# main-board.net
KiCad netlist of a schematic drawn in EAGLE
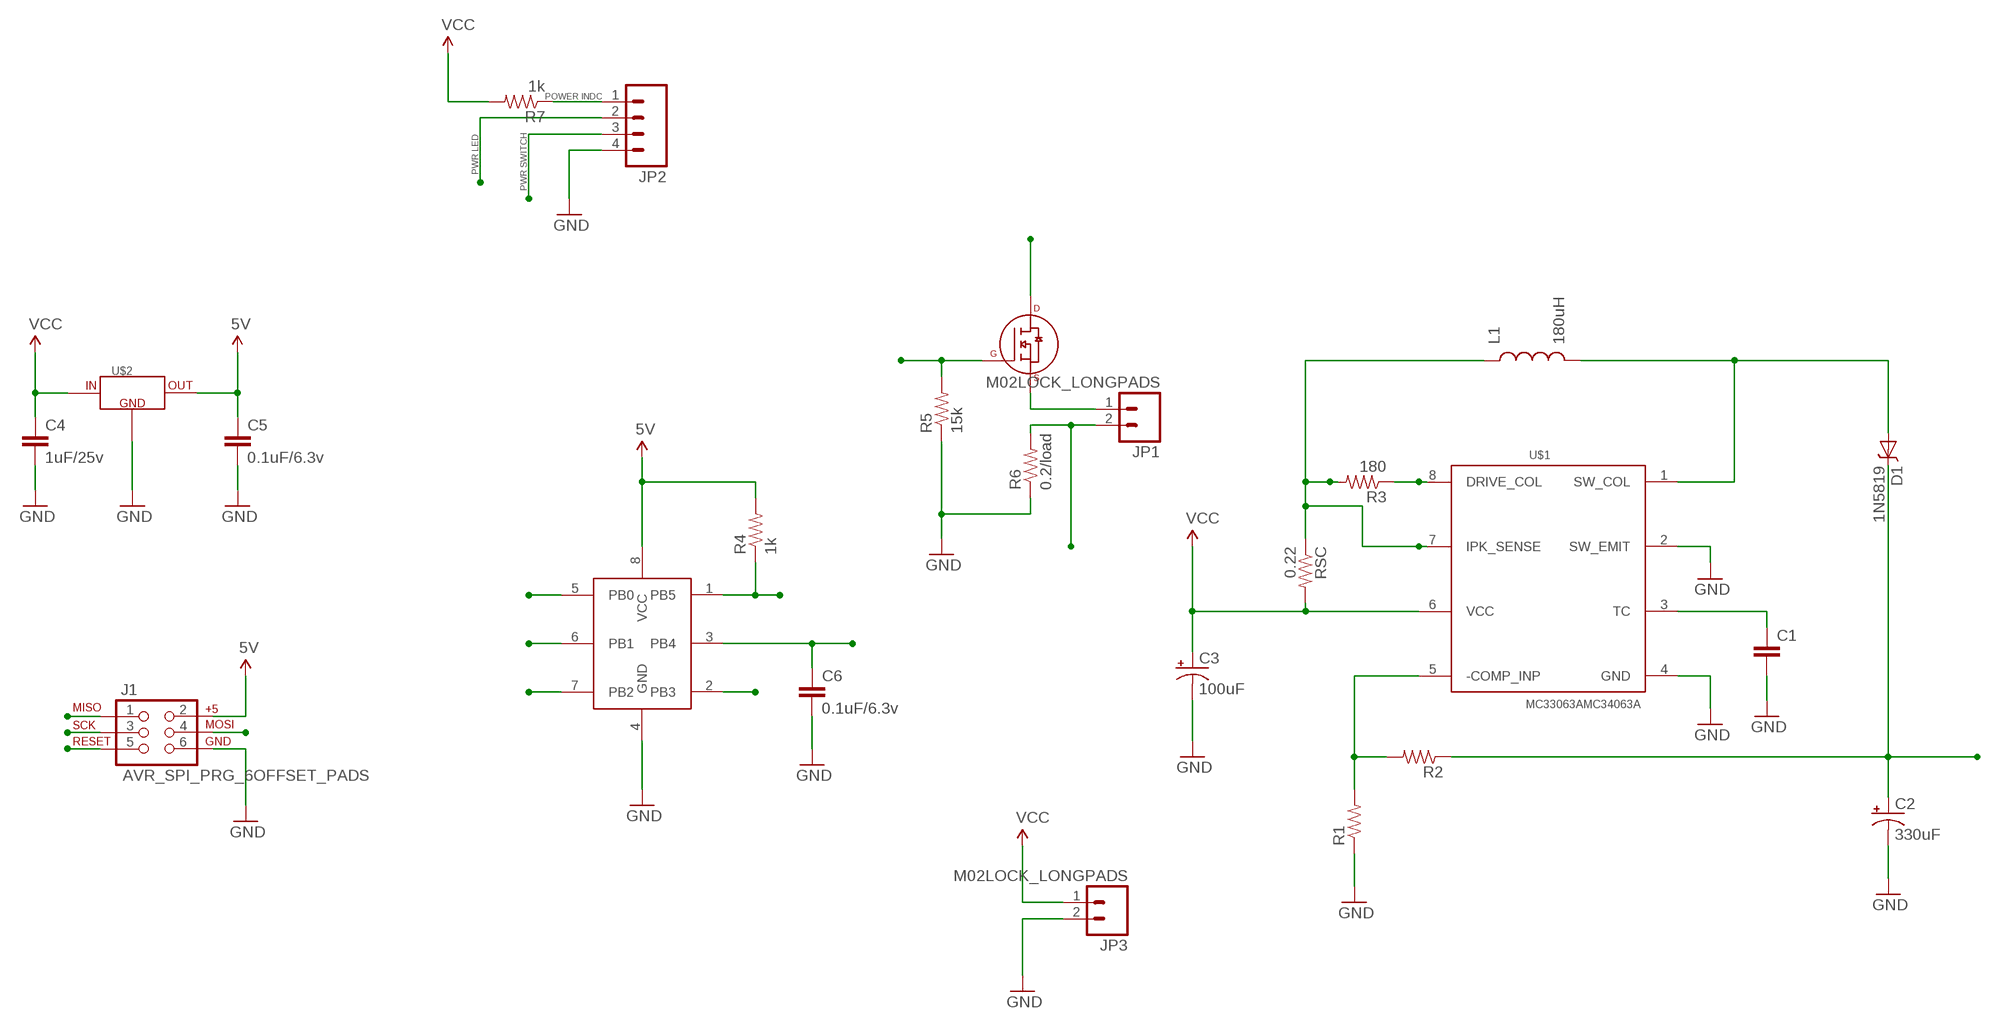
[diagram p0: schematic, sheet 1]

(export (version "E")
  (design (tool "Eeschema 10.0.6"))
  (components
    (comp (ref "C1")
      (value "CAP0603-CAP")
      (footprint "eagle-import:0603-CAP")
      (libsource (lib "eagle-import") (part "SparkFun-Passives_CAP0603-CAP"))
    )
    (comp (ref "C2")
      (value "330uF")
      (footprint "eagle-import:PANASONIC_D")
      (libsource (lib "eagle-import") (part "CPOL-USD"))
    )
    (comp (ref "C3")
      (value "100uF")
      (footprint "eagle-import:PANASONIC_D")
      (libsource (lib "eagle-import") (part "CPOL-USD"))
    )
    (comp (ref "C4")
      (value "1uF/25v")
      (footprint "eagle-import:0603-CAP")
      (libsource (lib "eagle-import") (part "CAP0603-CAP"))
    )
    (comp (ref "C5")
      (value "0.1uF/6.3v")
      (footprint "eagle-import:0603-CAP")
      (libsource (lib "eagle-import") (part "CAP0603-CAP"))
    )
    (comp (ref "C6")
      (value "0.1uF/6.3v")
      (footprint "eagle-import:0603-CAP")
      (libsource (lib "eagle-import") (part "CAP0603-CAP"))
    )
    (comp (ref "D1")
      (value "1N5819")
      (footprint "eagle-import:SMA-DIODE")
      (libsource (lib "eagle-import") (part "DIODE-SCHOTTKY_"))
    )
    (comp (ref "J1")
      (value "AVR_SPI_PRG_6OFFSET_PADS")
      (footprint "eagle-import:2X3_OFFSET")
      (libsource (lib "eagle-import") (part "AVR_SPI_PRG_6OFFSET_PADS"))
    )
    (comp (ref "JP1")
      (value "M02LOCK_LONGPADS")
      (footprint "eagle-import:1X02_LOCK_LONGPADS")
      (libsource (lib "eagle-import") (part "M02LOCK_LONGPADS"))
    )
    (comp (ref "JP2")
      (value "M04LONGPADS")
      (footprint "eagle-import:1X04_LONGPADS")
      (libsource (lib "eagle-import") (part "M04LONGPADS"))
    )
    (comp (ref "JP3")
      (value "M02LOCK_LONGPADS")
      (footprint "eagle-import:1X02_LOCK_LONGPADS")
      (libsource (lib "eagle-import") (part "M02LOCK_LONGPADS"))
    )
    (comp (ref "L1")
      (value "180uH")
      (footprint "eagle-import:CDRH125")
      (libsource (lib "eagle-import") (part "INDUCTORPWR"))
    )
    (comp (ref "R1")
      (value "RESISTOR0603")
      (footprint "eagle-import:0603-RES")
      (libsource (lib "eagle-import") (part "RESISTOR0603"))
    )
    (comp (ref "R2")
      (value "RESISTOR0603")
      (footprint "eagle-import:0603-RES")
      (libsource (lib "eagle-import") (part "RESISTOR0603"))
    )
    (comp (ref "R3")
      (value "180")
      (footprint "eagle-import:0603-RES")
      (libsource (lib "eagle-import") (part "RESISTOR0603"))
    )
    (comp (ref "R4")
      (value "1k")
      (footprint "eagle-import:0603-RES")
      (libsource (lib "eagle-import") (part "RESISTOR0603-RES"))
    )
    (comp (ref "R5")
      (value "15k")
      (footprint "eagle-import:0603-RES")
      (libsource (lib "eagle-import") (part "RESISTOR0603-RES"))
    )
    (comp (ref "R6")
      (value "0.2/load")
      (footprint "eagle-import:0805")
      (libsource (lib "eagle-import") (part "RESISTOR0805-RES"))
    )
    (comp (ref "R7")
      (value "1k")
      (footprint "eagle-import:0603-RES")
      (libsource (lib "eagle-import") (part "RESISTOR0603-RES"))
    )
    (comp (ref "RSC")
      (value "0.22")
      (footprint "eagle-import:0603-RES")
      (libsource (lib "eagle-import") (part "RESISTOR0603"))
    )
    (comp (ref "U$1")
      (value "MC33063AMC34063A")
      (footprint "eagle-import:SOIC-8")
      (libsource (lib "eagle-import") (part "MC33063AMC34063A"))
    )
    (comp (ref "U$2")
      (value "TPS715XX")
      (footprint "eagle-import:SC70-5")
      (libsource (lib "eagle-import") (part "TPS715XX"))
    )
    (comp (ref "U$3")
      (value "ATTINY13")
      (footprint "eagle-import:WSOIC-8")
      (libsource (lib "eagle-import") (part "ATTINY13"))
    )
    (comp (ref "U$4")
      (value "FQB30N06LTM")
      (footprint "eagle-import:TO-263AB")
      (libsource (lib "eagle-import") (part "FQB30N06LTM"))
    )
  )
  (nets
    (net (code "1") (name "/LED+") (class "Default")
      (node (ref "C2") (pin "+") (pinfunction "+_+") (pintype "passive"))
      (node (ref "D1") (pin "C") (pinfunction "C_C") (pintype "passive"))
      (node (ref "R2") (pin "1") (pinfunction "1_1") (pintype "passive"))
      (node (ref "U$4") (pin "4") (pinfunction "D_4") (pintype "bidirectional"))
    )
    (net (code "2") (name "/MISO") (class "Default")
      (node (ref "J1") (pin "1") (pinfunction "1_1") (pintype "passive"))
      (node (ref "U$3") (pin "6") (pinfunction "PB1_6") (pintype "bidirectional"))
    )
    (net (code "3") (name "/MOSI") (class "Default")
      (node (ref "J1") (pin "4") (pinfunction "4_4") (pintype "passive"))
      (node (ref "R5") (pin "2") (pinfunction "2_2") (pintype "passive"))
      (node (ref "U$3") (pin "5") (pinfunction "PB0_5") (pintype "bidirectional"))
      (node (ref "U$4") (pin "1") (pinfunction "G_1") (pintype "bidirectional"))
    )
    (net (code "4") (name "/PWR_LED") (class "Default")
      (node (ref "JP2") (pin "2") (pinfunction "2_2") (pintype "passive"))
      (node (ref "U$3") (pin "2") (pinfunction "PB3_2") (pintype "bidirectional"))
    )
    (net (code "5") (name "/RESET") (class "Default")
      (node (ref "J1") (pin "5") (pinfunction "5_5") (pintype "passive"))
      (node (ref "R4") (pin "1") (pinfunction "1_1") (pintype "passive"))
      (node (ref "U$3") (pin "1") (pinfunction "PB5_1") (pintype "bidirectional"))
    )
    (net (code "6") (name "/SCK") (class "Default")
      (node (ref "J1") (pin "3") (pinfunction "3_3") (pintype "passive"))
      (node (ref "JP2") (pin "3") (pinfunction "3_3") (pintype "passive"))
      (node (ref "U$3") (pin "7") (pinfunction "PB2_7") (pintype "bidirectional"))
    )
    (net (code "7") (name "/SENSE") (class "Default")
      (node (ref "C6") (pin "1") (pinfunction "1_1") (pintype "passive"))
      (node (ref "JP1") (pin "2") (pinfunction "2_2") (pintype "passive"))
      (node (ref "R6") (pin "2") (pinfunction "2_2") (pintype "passive"))
      (node (ref "U$3") (pin "3") (pinfunction "PB4_3") (pintype "bidirectional"))
    )
    (net (code "8") (name "5V") (class "Default")
      (node (ref "C5") (pin "1") (pinfunction "1_1") (pintype "passive"))
      (node (ref "J1") (pin "2") (pinfunction "2_2") (pintype "passive"))
      (node (ref "R4") (pin "2") (pinfunction "2_2") (pintype "passive"))
      (node (ref "U$2") (pin "5") (pinfunction "OUT_5") (pintype "bidirectional"))
      (node (ref "U$3") (pin "8") (pinfunction "VCC_8") (pintype "bidirectional"))
    )
    (net (code "9") (name "GND") (class "Default")
      (node (ref "C1") (pin "2") (pinfunction "2_2") (pintype "passive"))
      (node (ref "C2") (pin "-") (pinfunction "-_-") (pintype "passive"))
      (node (ref "C3") (pin "-") (pinfunction "-_-") (pintype "passive"))
      (node (ref "C4") (pin "2") (pinfunction "2_2") (pintype "passive"))
      (node (ref "C5") (pin "2") (pinfunction "2_2") (pintype "passive"))
      (node (ref "C6") (pin "2") (pinfunction "2_2") (pintype "passive"))
      (node (ref "J1") (pin "6") (pinfunction "6_6") (pintype "passive"))
      (node (ref "JP2") (pin "4") (pinfunction "4_4") (pintype "passive"))
      (node (ref "JP3") (pin "2") (pinfunction "2_2") (pintype "passive"))
      (node (ref "R1") (pin "1") (pinfunction "1_1") (pintype "passive"))
      (node (ref "R5") (pin "1") (pinfunction "1_1") (pintype "passive"))
      (node (ref "R6") (pin "1") (pinfunction "1_1") (pintype "passive"))
      (node (ref "U$1") (pin "2") (pinfunction "SW_EMIT_2") (pintype "bidirectional"))
      (node (ref "U$1") (pin "4") (pinfunction "GND_4") (pintype "bidirectional"))
      (node (ref "U$2") (pin "2") (pinfunction "GND_2") (pintype "bidirectional"))
      (node (ref "U$3") (pin "4") (pinfunction "GND_4") (pintype "bidirectional"))
    )
    (net (code "10") (name "Net-(JP2-Pad1)") (class "Default")
      (node (ref "JP2") (pin "1") (pinfunction "1_1") (pintype "passive"))
      (node (ref "R7") (pin "1") (pinfunction "1_1") (pintype "passive"))
    )
    (net (code "11") (name "Net-(U$1--COMP_INP)") (class "Default")
      (node (ref "R1") (pin "2") (pinfunction "2_2") (pintype "passive"))
      (node (ref "R2") (pin "2") (pinfunction "2_2") (pintype "passive"))
      (node (ref "U$1") (pin "5") (pinfunction "-COMP_INP_5") (pintype "bidirectional"))
    )
    (net (code "12") (name "Net-(U$1-DRIVE_COL)") (class "Default")
      (node (ref "R3") (pin "1") (pinfunction "1_1") (pintype "passive"))
      (node (ref "U$1") (pin "8") (pinfunction "DRIVE_COL_8") (pintype "bidirectional"))
    )
    (net (code "13") (name "Net-(U$1-IPK_SENSE)") (class "Default")
      (node (ref "L1") (pin "1") (pinfunction "1_1") (pintype "passive"))
      (node (ref "R3") (pin "2") (pinfunction "2_2") (pintype "passive"))
      (node (ref "RSC") (pin "1") (pinfunction "1_1") (pintype "passive"))
      (node (ref "U$1") (pin "7") (pinfunction "IPK_SENSE_7") (pintype "bidirectional"))
    )
    (net (code "14") (name "Net-(U$1-SW_COL)") (class "Default")
      (node (ref "D1") (pin "A") (pinfunction "A_A") (pintype "passive"))
      (node (ref "L1") (pin "2") (pinfunction "2_2") (pintype "passive"))
      (node (ref "U$1") (pin "1") (pinfunction "SW_COL_1") (pintype "bidirectional"))
    )
    (net (code "15") (name "Net-(U$1-TC)") (class "Default")
      (node (ref "C1") (pin "1") (pinfunction "1_1") (pintype "passive"))
      (node (ref "U$1") (pin "3") (pinfunction "TC_3") (pintype "bidirectional"))
    )
    (net (code "16") (name "Net-(U$4-S)") (class "Default")
      (node (ref "JP1") (pin "1") (pinfunction "1_1") (pintype "passive"))
      (node (ref "U$4") (pin "3") (pinfunction "S_3") (pintype "bidirectional"))
    )
    (net (code "17") (name "VCC") (class "Default")
      (node (ref "C3") (pin "+") (pinfunction "+_+") (pintype "passive"))
      (node (ref "C4") (pin "1") (pinfunction "1_1") (pintype "passive"))
      (node (ref "JP3") (pin "1") (pinfunction "1_1") (pintype "passive"))
      (node (ref "R7") (pin "2") (pinfunction "2_2") (pintype "passive"))
      (node (ref "RSC") (pin "2") (pinfunction "2_2") (pintype "passive"))
      (node (ref "U$1") (pin "6") (pinfunction "VCC_6") (pintype "bidirectional"))
      (node (ref "U$2") (pin "4") (pinfunction "IN_4") (pintype "bidirectional"))
    )
  )
)
